# P09_Ethernet.net
KiCad netlist of a schematic drawn in Altium Designer
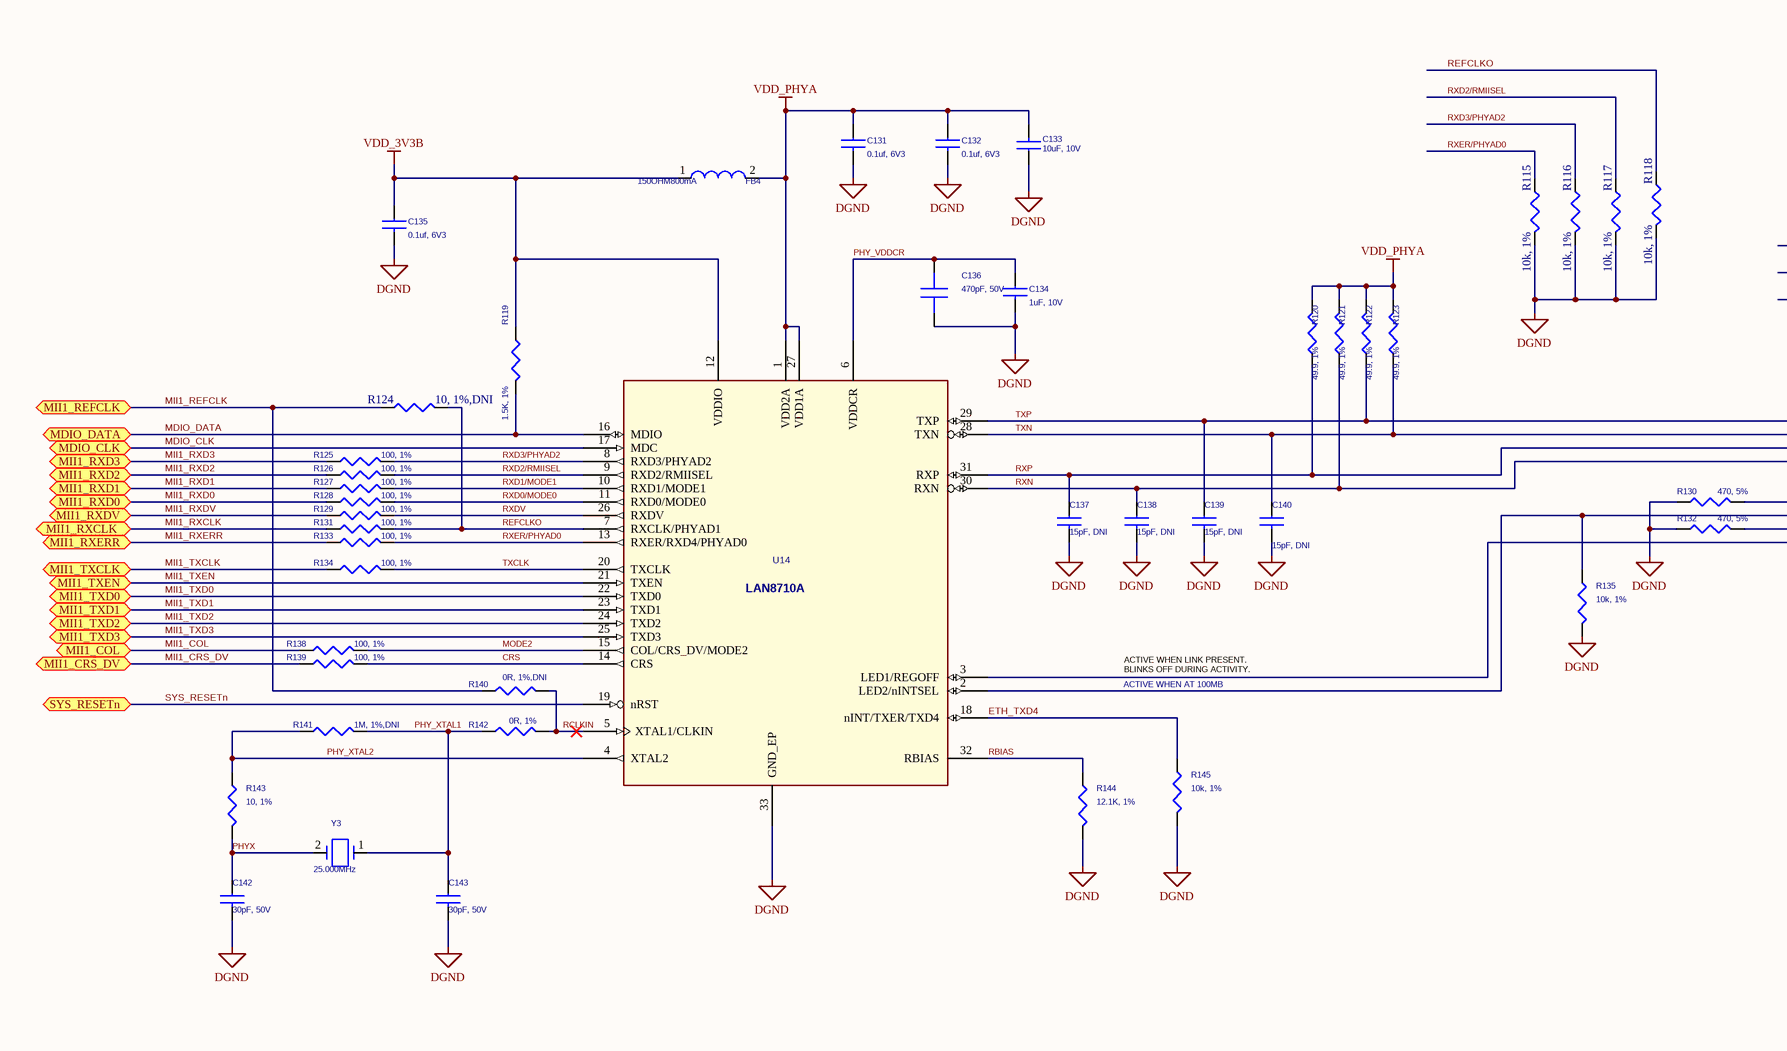
[diagram p0: P09_Ethernet.SchDoc, left]
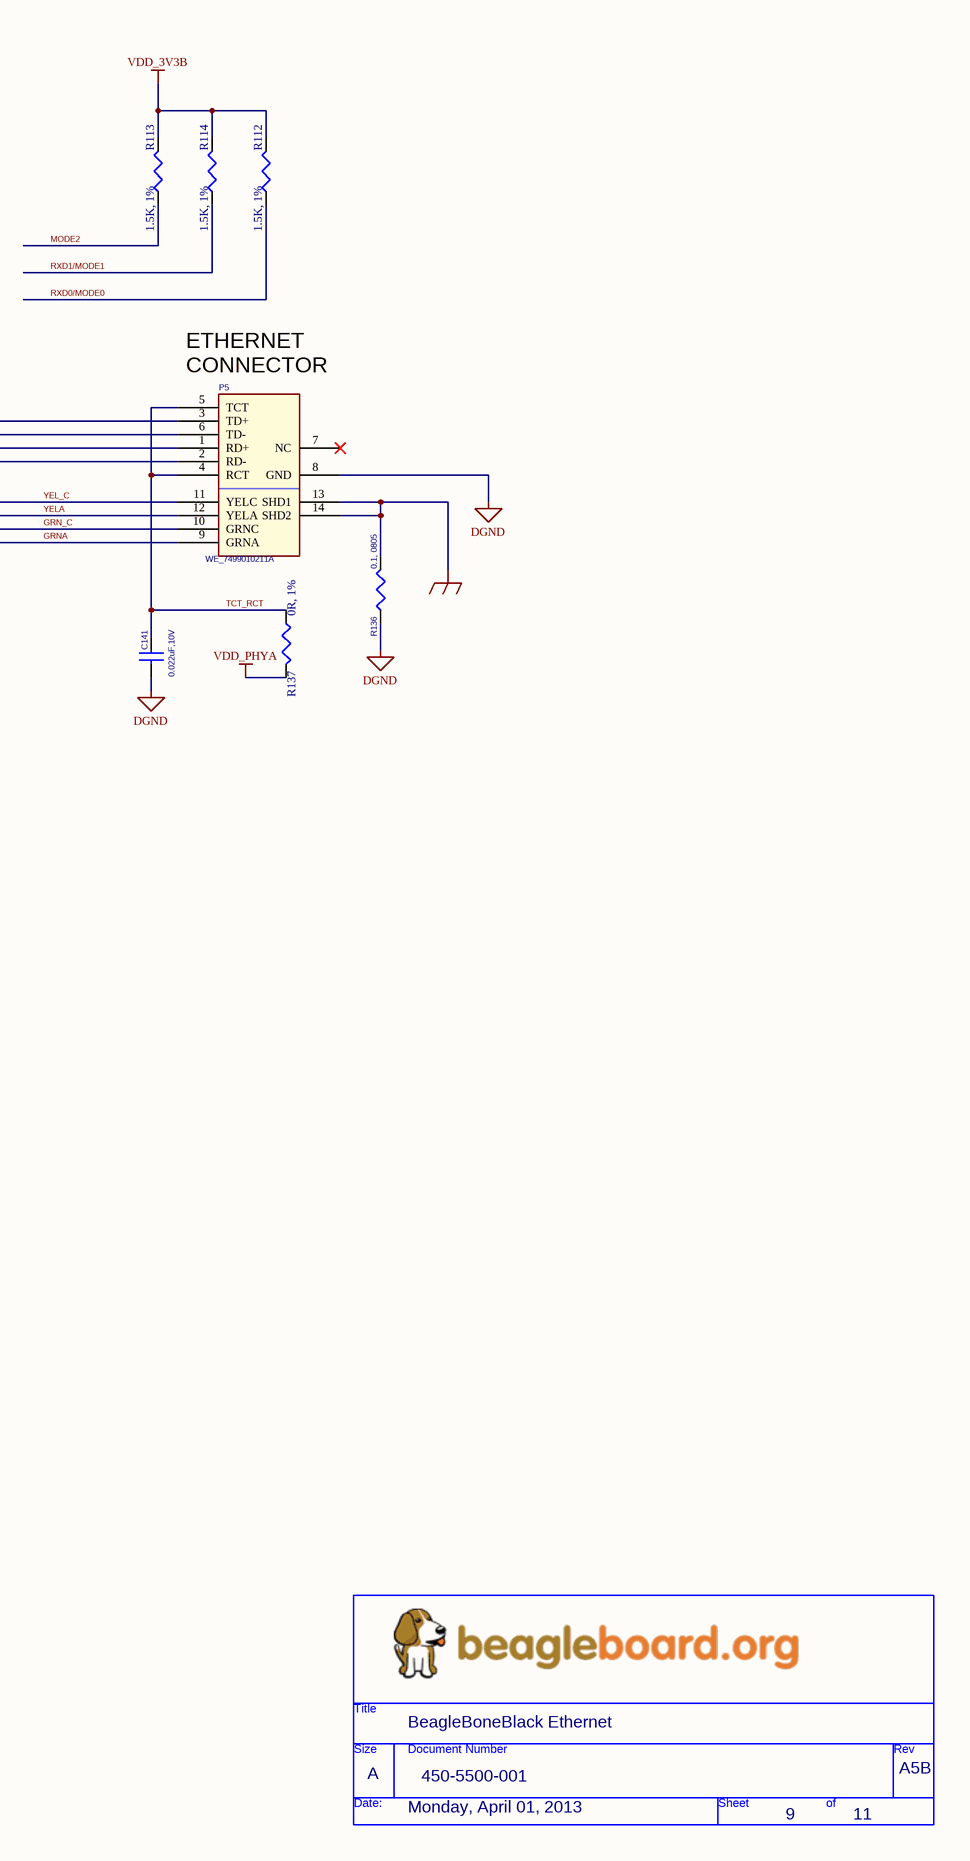
[diagram p1: P09_Ethernet.SchDoc, right]

(export (version "E")
  (design (tool "Eeschema 10.0.6"))
  (components
    (comp (ref "C131")
      (value "0.1uf, 6V3")
      (footprint "402")
      (description "CAP CER 0.1UF 6.3V 10% X5R 0402")
      (fields
        (field (name "MANUFACTURER") "TDK Corporation")
        (field (name "MANUFACTURER PART NUMBER") "C1005X5R0J104K050BA")
      )
      (libsource (lib "BEAGLEBONEBLACK_REV A5B") (part "CAP_0.1uF_X7R_16V_10% 0402"))
    )
    (comp (ref "C132")
      (value "0.1uf, 6V3")
      (footprint "402")
      (description "CAP CER 0.1UF 6.3V 10% X5R 0402")
      (fields
        (field (name "MANUFACTURER") "TDK Corporation")
        (field (name "MANUFACTURER PART NUMBER") "C1005X5R0J104K050BA")
      )
      (libsource (lib "BEAGLEBONEBLACK_REV A5B") (part "CAP_0.1uF_X7R_16V_10% 0402"))
    )
    (comp (ref "C133")
      (value "10uF, 10V")
      (footprint "805")
      (description "CAP CER 10UF 10V Y5V 0805")
      (fields
        (field (name "MANUFACTURER") "TDK Corporation")
        (field (name "MANUFACTURER PART NUMBER") "C2012Y5V1A106Z")
      )
      (libsource (lib "BEAGLEBONEBLACK_REV A5B") (part "CAP_4.7uF_X5R_6.3V_10%_0603"))
    )
    (comp (ref "C134")
      (value "1uF, 10V")
      (footprint "402")
      (description "CAP CER 1UF 10V 10% X5R 0402")
      (fields
        (field (name "MANUFACTURER") "AVX Corporation")
        (field (name "MANUFACTURER PART NUMBER") "0402ZD105KAT2A")
      )
      (libsource (lib "BEAGLEBONEBLACK_REV A5B") (part "CAP_1.0UF_X5R_10V_10%_0402"))
    )
    (comp (ref "C135")
      (value "0.1uf, 6V3")
      (footprint "402")
      (description "CAP CER 0.1UF 6.3V 10% X5R 0402")
      (fields
        (field (name "MANUFACTURER") "TDK Corporation")
        (field (name "MANUFACTURER PART NUMBER") "C1005X5R0J104K050BA")
      )
      (libsource (lib "BEAGLEBONEBLACK_REV A5B") (part "CAP_0.1uF_X7R_16V_10% 0402"))
    )
    (comp (ref "C136")
      (value "470pF, 50V")
      (footprint "402")
      (description "CAP CER 470PF 50V 10% X7R 0402")
      (fields
        (field (name "MANUFACTURER") "Murata Electronics North America")
        (field (name "MANUFACTURER PART NUMBER") "GRM155R71H471KA01D")
      )
      (libsource (lib "BEAGLEBONEBLACK_REV A5B") (part "470pF/5%/50V/C0G/0603_0"))
    )
    (comp (ref "C137")
      (value "15pF, DNI")
      (footprint "402")
      (description "CAP CER 15PF 50V 5% NP0 0402")
      (fields
        (field (name "MANUFACTURER") "TDK Corporation")
        (field (name "MANUFACTURER PART NUMBER") "C1005C0G1H150J050BA")
      )
      (libsource (lib "BEAGLEBONEBLACK_REV A5B") (part "CAP_0402_100pF_COG_50V"))
    )
    (comp (ref "C138")
      (value "15pF, DNI")
      (footprint "402")
      (description "CAP CER 15PF 50V 5% NP0 0402")
      (fields
        (field (name "MANUFACTURER") "TDK Corporation")
        (field (name "MANUFACTURER PART NUMBER") "C1005C0G1H150J050BA")
      )
      (libsource (lib "BEAGLEBONEBLACK_REV A5B") (part "CAP_0402_100pF_COG_50V"))
    )
    (comp (ref "C139")
      (value "15pF, DNI")
      (footprint "402")
      (description "CAP CER 15PF 50V 5% NP0 0402")
      (fields
        (field (name "MANUFACTURER") "TDK Corporation")
        (field (name "MANUFACTURER PART NUMBER") "C1005C0G1H150J050BA")
      )
      (libsource (lib "BEAGLEBONEBLACK_REV A5B") (part "CAP_0402_100pF_COG_50V"))
    )
    (comp (ref "C140")
      (value "15pF, DNI")
      (footprint "402")
      (description "CAP CER 15PF 50V 5% NP0 0402")
      (fields
        (field (name "MANUFACTURER") "TDK Corporation")
        (field (name "MANUFACTURER PART NUMBER") "C1005C0G1H150J050BA")
      )
      (libsource (lib "BEAGLEBONEBLACK_REV A5B") (part "CAP_0402_100pF_COG_50V"))
    )
    (comp (ref "C141")
      (value "0.022uF,10V")
      (footprint "402")
      (description "CAP CER 0.022UF 10V 10% X7R 0402")
      (fields
        (field (name "MANUFACTURER") "Taiyo Yuden")
        (field (name "MANUFACTURER PART NUMBER") "LMK105B7223KV-F")
      )
      (libsource (lib "BEAGLEBONEBLACK_REV A5B") (part "CAP_0402_0.1uf_X5R_10V"))
    )
    (comp (ref "C142")
      (value "30pF, 50V")
      (footprint "402")
      (description "CAP CER 30PF 50V 5% NP0 0402")
      (fields
        (field (name "MANUFACTURER") "TDK Corporation")
        (field (name "MANUFACTURER PART NUMBER") "C1005C0G1H300J")
      )
      (libsource (lib "BEAGLEBONEBLACK_REV A5B") (part "CAP_30PF_COG_50V_5%_0402"))
    )
    (comp (ref "C143")
      (value "30pF, 50V")
      (footprint "402")
      (description "CAP CER 30PF 50V 5% NP0 0402")
      (fields
        (field (name "MANUFACTURER") "TDK Corporation")
        (field (name "MANUFACTURER PART NUMBER") "C1005C0G1H300J")
      )
      (libsource (lib "BEAGLEBONEBLACK_REV A5B") (part "CAP_30PF_COG_50V_5%_0402"))
    )
    (comp (ref "FB4")
      (value "150OHM800mA")
      (footprint "SM-7351-IND-0805")
      (description "FERRITE 800MA 150 OHM 0805 SMD")
      (fields (field (name "MFR") "Steward") (field (name "TIINTPARTNUMBER") "1L0010"))
      (libsource (lib "BEAGLEBONEBLACK_REV A5B") (part "FER_180_200_0"))
    )
    (comp (ref "P5")
      (value "WE_7499010211A")
      (description "WE-RJ45 LAN Transformer")
      (libsource (lib "BEAGLEBONEBLACK_REV A5B") (part "CONN_RJ45_MAG_WE_0"))
    )
    (comp (ref "R112")
      (value "1.5K, 1%")
      (footprint "402")
      (description "RES 1.50K OHM 1/16W 1% 0402 SMD")
      (fields
        (field (name "MANUFACTURER") "Yageo")
        (field (name "MANUFACTURER PART NUMBER") "RC0402FR-071K5L")
      )
      (libsource (lib "BEAGLEBONEBLACK_REV A5B") (part "RES_10K_1/16W_1%_0402"))
    )
    (comp (ref "R113")
      (value "1.5K, 1%")
      (footprint "402")
      (description "RES 1.50K OHM 1/16W 1% 0402 SMD")
      (fields
        (field (name "MANUFACTURER") "Yageo")
        (field (name "MANUFACTURER PART NUMBER") "RC0402FR-071K5L")
      )
      (libsource (lib "BEAGLEBONEBLACK_REV A5B") (part "RES_10K_1/16W_1%_0402"))
    )
    (comp (ref "R114")
      (value "1.5K, 1%")
      (footprint "402")
      (description "RES 1.50K OHM 1/16W 1% 0402 SMD")
      (fields
        (field (name "MANUFACTURER") "Yageo")
        (field (name "MANUFACTURER PART NUMBER") "RC0402FR-071K5L")
      )
      (libsource (lib "BEAGLEBONEBLACK_REV A5B") (part "RES_10K_1/16W_1%_0402"))
    )
    (comp (ref "R115")
      (value "10k, 1%")
      (footprint "402")
      (description "RES 10K OHM 1/16W 5% 0402 SMD")
      (fields
        (field (name "MANUFACTURER") "Rohm Semiconductor")
        (field (name "MANUFACTURER PART NUMBER") "MCR01MZPJ103")
      )
      (libsource (lib "BEAGLEBONEBLACK_REV A5B") (part "RES_10K_1/16W_1%_0402"))
    )
    (comp (ref "R116")
      (value "10k, 1%")
      (footprint "402")
      (description "RES 10K OHM 1/16W 5% 0402 SMD")
      (fields
        (field (name "MANUFACTURER") "Rohm Semiconductor")
        (field (name "MANUFACTURER PART NUMBER") "MCR01MZPJ103")
      )
      (libsource (lib "BEAGLEBONEBLACK_REV A5B") (part "RES_10K_1/16W_1%_0402"))
    )
    (comp (ref "R117")
      (value "10k, 1%")
      (footprint "402")
      (description "RES 10K OHM 1/16W 5% 0402 SMD")
      (fields
        (field (name "MANUFACTURER") "Rohm Semiconductor")
        (field (name "MANUFACTURER PART NUMBER") "MCR01MZPJ103")
      )
      (libsource (lib "BEAGLEBONEBLACK_REV A5B") (part "RES_10K_1/16W_1%_0402"))
    )
    (comp (ref "R118")
      (value "10k, 1%")
      (footprint "402")
      (description "RES 10K OHM 1/16W 5% 0402 SMD")
      (fields
        (field (name "MANUFACTURER") "Rohm Semiconductor")
        (field (name "MANUFACTURER PART NUMBER") "MCR01MZPJ103")
      )
      (libsource (lib "BEAGLEBONEBLACK_REV A5B") (part "RES_10K_1/16W_1%_0402"))
    )
    (comp (ref "R119")
      (value "1.5K, 1%")
      (footprint "402")
      (description "RES 1.50K OHM 1/16W 1% 0402 SMD")
      (fields
        (field (name "MANUFACTURER") "Yageo")
        (field (name "MANUFACTURER PART NUMBER") "RC0402FR-071K5L")
      )
      (libsource (lib "BEAGLEBONEBLACK_REV A5B") (part "RES_1.5K_1/16W_5%_0402"))
    )
    (comp (ref "R120")
      (value "49.9, 1%")
      (footprint "402")
      (description "RES 49.9 OHM 1/16W 1% 0402 SMD")
      (fields
        (field (name "MANUFACTURER") "Yageo")
        (field (name "MANUFACTURER PART NUMBER") "RC0402FR-0749R9L")
      )
      (libsource (lib "BEAGLEBONEBLACK_REV A5B") (part "RES_4.7K_0402"))
    )
    (comp (ref "R121")
      (value "49.9, 1%")
      (footprint "402")
      (description "RES 49.9 OHM 1/16W 1% 0402 SMD")
      (fields
        (field (name "MANUFACTURER") "Yageo")
        (field (name "MANUFACTURER PART NUMBER") "RC0402FR-0749R9L")
      )
      (libsource (lib "BEAGLEBONEBLACK_REV A5B") (part "RES_4.7K_0402"))
    )
    (comp (ref "R122")
      (value "49.9, 1%")
      (footprint "402")
      (description "RES 49.9 OHM 1/16W 1% 0402 SMD")
      (fields
        (field (name "MANUFACTURER") "Yageo")
        (field (name "MANUFACTURER PART NUMBER") "RC0402FR-0749R9L")
      )
      (libsource (lib "BEAGLEBONEBLACK_REV A5B") (part "RES_4.7K_0402"))
    )
    (comp (ref "R123")
      (value "49.9, 1%")
      (footprint "402")
      (description "RES 49.9 OHM 1/16W 1% 0402 SMD")
      (fields
        (field (name "MANUFACTURER") "Yageo")
        (field (name "MANUFACTURER PART NUMBER") "RC0402FR-0749R9L")
      )
      (libsource (lib "BEAGLEBONEBLACK_REV A5B") (part "RES_4.7K_0402"))
    )
    (comp (ref "R124")
      (value "10, 1%,DNI")
      (footprint "402")
      (description "Resistor 10Kohm 1/16W 1% 0402")
      (fields
        (field (name "MANUFACTURER") "Stackpole Electronics Inc")
        (field (name "MANUFACTURER PART NUMBER") "RMCF0402FT10R0")
      )
      (libsource (lib "BEAGLEBONEBLACK_REV A5B") (part "RES_10K_1/16W_1%_0402"))
    )
    (comp (ref "R125")
      (value "100, 1%")
      (footprint "402")
      (description "RES 100 OHM 1/10W 5% 0402 SMD")
      (fields
        (field (name "PART#") "Rohm MCR03EZPFX1000")
        (field (name "MANUFACTURER") "Panasonic Electronic Components")
      )
      (libsource (lib "BEAGLEBONEBLACK_REV A5B") (part "100-1/10W-1%-0603_4"))
    )
    (comp (ref "R126")
      (value "100, 1%")
      (footprint "402")
      (description "RES 100 OHM 1/10W 5% 0402 SMD")
      (fields
        (field (name "PART#") "Rohm MCR03EZPFX1000")
        (field (name "MANUFACTURER") "Panasonic Electronic Components")
      )
      (libsource (lib "BEAGLEBONEBLACK_REV A5B") (part "100-1/10W-1%-0603_4"))
    )
    (comp (ref "R127")
      (value "100, 1%")
      (footprint "402")
      (description "RES 100 OHM 1/10W 5% 0402 SMD")
      (fields
        (field (name "MANUFACTURER") "Panasonic Electronic Components")
        (field (name "MANUFACTURER PART NUMBER") "ERJ-2RKF1000X")
      )
      (libsource (lib "BEAGLEBONEBLACK_REV A5B") (part "RES_100_1/10W_5%_0402"))
    )
    (comp (ref "R128")
      (value "100, 1%")
      (footprint "402")
      (description "RES 100 OHM 1/10W 5% 0402 SMD")
      (fields
        (field (name "MANUFACTURER") "Panasonic Electronic Components")
        (field (name "MANUFACTURER PART NUMBER") "ERJ-2RKF1000X")
      )
      (libsource (lib "BEAGLEBONEBLACK_REV A5B") (part "RES_100_1/10W_5%_0402"))
    )
    (comp (ref "R129")
      (value "100, 1%")
      (footprint "402")
      (description "RES 100 OHM 1/10W 5% 0402 SMD")
      (fields
        (field (name "PART#") "Rohm MCR03EZPFX1000")
        (field (name "MANUFACTURER") "Panasonic Electronic Components")
      )
      (libsource (lib "BEAGLEBONEBLACK_REV A5B") (part "100-1/10W-1%-0603_4"))
    )
    (comp (ref "R130")
      (value "470, 5%")
      (footprint "402")
      (description "RES 470 OHM 1/10W 5% 0402 SMD")
      (fields
        (field (name "MANUFACTURER") "Panasonic Electronic Components")
        (field (name "MANUFACTURER PART NUMBER") "ERJ-2GEJ471X")
      )
      (libsource (lib "BEAGLEBONEBLACK_REV A5B") (part "RES_470_1/10W_5%_0402"))
    )
    (comp (ref "R131")
      (value "100, 1%")
      (footprint "402")
      (description "RES 100 OHM 1/10W 5% 0402 SMD")
      (fields
        (field (name "MANUFACTURER") "Panasonic Electronic Components")
        (field (name "MANUFACTURER PART NUMBER") "ERJ-2RKF1000X")
      )
      (libsource (lib "BEAGLEBONEBLACK_REV A5B") (part "RES_100_1/10W_5%_0402"))
    )
    (comp (ref "R132")
      (value "470, 5%")
      (footprint "402")
      (description "RES 470 OHM 1/10W 5% 0402 SMD")
      (fields
        (field (name "MANUFACTURER") "Panasonic Electronic Components")
        (field (name "MANUFACTURER PART NUMBER") "ERJ-2GEJ471X")
      )
      (libsource (lib "BEAGLEBONEBLACK_REV A5B") (part "RES_470_1/10W_5%_0402"))
    )
    (comp (ref "R133")
      (value "100, 1%")
      (footprint "402")
      (description "RES 100 OHM 1/10W 5% 0402 SMD")
      (fields
        (field (name "MANUFACTURER") "Panasonic Electronic Components")
        (field (name "MANUFACTURER PART NUMBER") "ERJ-2RKF1000X")
      )
      (libsource (lib "BEAGLEBONEBLACK_REV A5B") (part "RES_100_1/10W_5%_0402"))
    )
    (comp (ref "R134")
      (value "100, 1%")
      (footprint "402")
      (description "RES 100 OHM 1/10W 5% 0402 SMD")
      (fields (field (name "PART#") "Rohm MCR03EZPFX1000") (field (name "TOLERANCE") "1%"))
      (libsource (lib "BEAGLEBONEBLACK_REV A5B") (part "100-1/10W-1%-0603_4"))
    )
    (comp (ref "R135")
      (value "10k, 1%")
      (footprint "402")
      (description "RES 10K OHM 1/16W 5% 0402 SMD")
      (fields
        (field (name "MANUFACTURER") "Rohm Semiconductor")
        (field (name "MANUFACTURER PART NUMBER") "MCR01MZPJ103")
      )
      (libsource (lib "BEAGLEBONEBLACK_REV A5B") (part "RES_10K_1/16W_1%_0402"))
    )
    (comp (ref "R136")
      (value "0.1, 0805")
      (description "RES .10 OHM 1/8W 5% 0805")
      (fields
        (field (name "MANUFACTURER") "CTS Resistor Products")
        (field (name "MANUFACTURER PART NUMBER") "73L3R10J")
      )
      (libsource (lib "BEAGLEBONEBLACK_REV A5B") (part "RES_0.1_0805"))
    )
    (comp (ref "R137")
      (value "0R, 1%")
      (footprint "402")
      (description "RES 0.0 OHM 1/16W 0402 SMD")
      (fields
        (field (name "MANUFACTURER") "Yageo")
        (field (name "MANUFACTURER PART NUMBER") "RC0402JR-070RL")
      )
      (libsource (lib "BEAGLEBONEBLACK_REV A5B") (part "RES_0_1/16W_1%_0402"))
    )
    (comp (ref "R138")
      (value "100, 1%")
      (footprint "402")
      (description "RES 100 OHM 1/10W 5% 0402 SMD")
      (fields (field (name "PART#") "Rohm MCR03EZPFX1000") (field (name "TOLERANCE") "1%"))
      (libsource (lib "BEAGLEBONEBLACK_REV A5B") (part "100-1/10W-1%-0603_4"))
    )
    (comp (ref "R139")
      (value "100, 1%")
      (footprint "402")
      (description "RES 100 OHM 1/10W 5% 0402 SMD")
      (fields
        (field (name "MANUFACTURER") "Panasonic Electronic Components")
        (field (name "MANUFACTURER PART NUMBER") "ERJ-2RKF1000X")
      )
      (libsource (lib "BEAGLEBONEBLACK_REV A5B") (part "RES_100_1/10W_5%_0402"))
    )
    (comp (ref "R140")
      (value "0R, 1%,DNI")
      (footprint "402")
      (description "RES 0.0 OHM 1/16W 0402 SMD")
      (fields
        (field (name "MANUFACTURER") "Yageo")
        (field (name "MANUFACTURER PART NUMBER") "RC0402JR-070RL")
      )
      (libsource (lib "BEAGLEBONEBLACK_REV A5B") (part "RES_0_1/16W_1%_0402"))
    )
    (comp (ref "R141")
      (value "1M, 1%,DNI")
      (footprint "402")
      (description "RES 1M OHM 1/16W 1% 0402 SMD")
      (fields
        (field (name "MANUFACTURER") "Stackpole Electronics Inc")
        (field (name "MANUFACTURER PART NUMBER") "RMCF0402FT1M00")
      )
      (libsource (lib "BEAGLEBONEBLACK_REV A5B") (part "RES_1M_1/16W_1%_0402"))
    )
    (comp (ref "R142")
      (value "0R, 1%")
      (footprint "402")
      (description "RES 0.0 OHM 1/16W 0402 SMD")
      (fields
        (field (name "MANUFACTURER") "Yageo")
        (field (name "MANUFACTURER PART NUMBER") "RC0402JR-070RL")
      )
      (libsource (lib "BEAGLEBONEBLACK_REV A5B") (part "RES_0_1/16W_1%_0402"))
    )
    (comp (ref "R143")
      (value "10, 1%")
      (footprint "402")
      (description "RES 10 OHM 1/16W 1% 0402 SMD")
      (fields
        (field (name "MANUFACTURER") "Stackpole Electronics Inc")
        (field (name "MANUFACTURER PART NUMBER") "RMCF0402FT10R0")
      )
      (libsource (lib "BEAGLEBONEBLACK_REV A5B") (part "RES_10K_1/16W_1%_0402"))
    )
    (comp (ref "R144")
      (value "12.1K, 1%")
      (footprint "402")
      (description "RES 12.1K OHM 1/16W 1% 0402 SMD")
      (fields
        (field (name "MANUFACTURER") "Yageo")
        (field (name "MANUFACTURER PART NUMBER") "RC0402FR-0712K1L")
      )
      (libsource (lib "BEAGLEBONEBLACK_REV A5B") (part "RES_12.1K_1/16W_1%_0402"))
    )
    (comp (ref "R145")
      (value "10k, 1%")
      (footprint "402")
      (description "RES 10K OHM 1/16W 5% 0402 SMD")
      (fields
        (field (name "MANUFACTURER") "Rohm Semiconductor")
        (field (name "MANUFACTURER PART NUMBER") "MCR01MZPJ103")
      )
      (libsource (lib "BEAGLEBONEBLACK_REV A5B") (part "RES_10K_1/16W_1%_0402"))
    )
    (comp (ref "U14")
      (value "LAN8710A")
      (footprint "QFN32_5X5MM_EP3P3MM")
      (description "Ethernet ICs 10/100 Ethernet XCVR w/HPAutoMDIX FlexPwr")
      (fields (field (name "PART#") "SMSC LAN8710A-EZK") (field (name "MANUFACTURER") "Microchip Technology"))
      (libsource (lib "BEAGLEBONEBLACK_REV A5B") (part "LAN8710 QFN32_1"))
    )
    (comp (ref "Y3")
      (value "25.000MHz")
      (footprint "XTAL150SMD_125X196")
      (fields
        (field (name "MANUFACTURER") "Abracon Corporation")
        (field (name "MANUFACTURER PART NUMBER") "ABM3-25.000MHZ-B2-T")
      )
      (libsource (lib "BEAGLEBONEBLACK_REV A5B") (part "Suntsu ITEMP 25MHz _0.005% 20pf"))
    )
  )
  (nets
    (net (code "1") (name "/CRS") (class "Default")
      (node (ref "R139") (pin "2") (pinfunction "2_2") (pintype "passive"))
      (node (ref "U14") (pin "14") (pinfunction "CRS_14") (pintype "output"))
    )
    (net (code "2") (name "/ETH_TXD4") (class "Default")
      (node (ref "R145") (pin "1") (pinfunction "1_1") (pintype "passive"))
      (node (ref "U14") (pin "18") (pinfunction "nINT/TXER/TXD4_18") (pintype "bidirectional"))
    )
    (net (code "3") (name "/GRNA") (class "Default")
      (node (ref "P5") (pin "9") (pinfunction "GRNA_9") (pintype "passive"))
      (node (ref "U14") (pin "3") (pinfunction "LED1/REGOFF_3") (pintype "bidirectional"))
    )
    (net (code "4") (name "/GRN_C") (class "Default")
      (node (ref "P5") (pin "10") (pinfunction "GRNC_10") (pintype "passive"))
      (node (ref "R132") (pin "2") (pinfunction "2_2") (pintype "passive"))
    )
    (net (code "5") (name "/MDIO_CLK") (class "Default")
      (node (ref "U14") (pin "17") (pinfunction "MDC_17") (pintype "input"))
    )
    (net (code "6") (name "/MDIO_DATA") (class "Default")
      (node (ref "R119") (pin "2") (pinfunction "2_2") (pintype "passive"))
      (node (ref "U14") (pin "16") (pinfunction "MDIO_16") (pintype "bidirectional"))
    )
    (net (code "7") (name "/MII1_COL") (class "Default")
      (node (ref "R138") (pin "1") (pinfunction "1_1") (pintype "passive"))
    )
    (net (code "8") (name "/MII1_CRS_DV") (class "Default")
      (node (ref "R139") (pin "1") (pinfunction "1_1") (pintype "passive"))
    )
    (net (code "9") (name "/MII1_REFCLK") (class "Default")
      (node (ref "R124") (pin "1") (pinfunction "1_1") (pintype "passive"))
      (node (ref "R140") (pin "1") (pinfunction "1_1") (pintype "passive"))
    )
    (net (code "10") (name "/MII1_RXCLK") (class "Default")
      (node (ref "R131") (pin "1") (pinfunction "1_1") (pintype "passive"))
    )
    (net (code "11") (name "/MII1_RXD0") (class "Default")
      (node (ref "R128") (pin "1") (pinfunction "1_1") (pintype "passive"))
    )
    (net (code "12") (name "/MII1_RXD1") (class "Default")
      (node (ref "R127") (pin "1") (pinfunction "1_1") (pintype "passive"))
    )
    (net (code "13") (name "/MII1_RXD2") (class "Default")
      (node (ref "R126") (pin "1") (pinfunction "1_1") (pintype "passive"))
    )
    (net (code "14") (name "/MII1_RXD3") (class "Default")
      (node (ref "R125") (pin "1") (pinfunction "1_1") (pintype "passive"))
    )
    (net (code "15") (name "/MII1_RXDV") (class "Default")
      (node (ref "R129") (pin "1") (pinfunction "1_1") (pintype "passive"))
    )
    (net (code "16") (name "/MII1_RXERR") (class "Default")
      (node (ref "R133") (pin "1") (pinfunction "1_1") (pintype "passive"))
    )
    (net (code "17") (name "/MII1_TXCLK") (class "Default")
      (node (ref "R134") (pin "1") (pinfunction "1_1") (pintype "passive"))
    )
    (net (code "18") (name "/MII1_TXD0") (class "Default")
      (node (ref "U14") (pin "22") (pinfunction "TXD0_22") (pintype "input"))
    )
    (net (code "19") (name "/MII1_TXD1") (class "Default")
      (node (ref "U14") (pin "23") (pinfunction "TXD1_23") (pintype "input"))
    )
    (net (code "20") (name "/MII1_TXD2") (class "Default")
      (node (ref "U14") (pin "24") (pinfunction "TXD2_24") (pintype "input"))
    )
    (net (code "21") (name "/MII1_TXD3") (class "Default")
      (node (ref "U14") (pin "25") (pinfunction "TXD3_25") (pintype "input"))
    )
    (net (code "22") (name "/MII1_TXEN") (class "Default")
      (node (ref "U14") (pin "21") (pinfunction "TXEN_21") (pintype "input"))
    )
    (net (code "23") (name "/MODE2") (class "Default")
      (node (ref "R113") (pin "1") (pinfunction "1_1") (pintype "passive"))
      (node (ref "R138") (pin "2") (pinfunction "2_2") (pintype "passive"))
      (node (ref "U14") (pin "15") (pinfunction "COL/CRS_DV/MODE2_15") (pintype "output"))
    )
    (net (code "24") (name "/PHYX") (class "Default")
      (node (ref "C142") (pin "1") (pinfunction "1_1") (pintype "passive"))
      (node (ref "R143") (pin "2") (pinfunction "2_2") (pintype "passive"))
      (node (ref "Y3") (pin "2") (pinfunction "2_2") (pintype "passive"))
    )
    (net (code "25") (name "/PHY_VDDCR") (class "Default")
      (node (ref "C134") (pin "1") (pinfunction "1_1") (pintype "passive"))
      (node (ref "C136") (pin "1") (pinfunction "1_1") (pintype "passive"))
      (node (ref "U14") (pin "6") (pinfunction "VDDCR_6") (pintype "power_in"))
    )
    (net (code "26") (name "/PHY_XTAL1") (class "Default")
      (node (ref "C143") (pin "1") (pinfunction "1_1") (pintype "passive"))
      (node (ref "R141") (pin "2") (pinfunction "2_2") (pintype "passive"))
      (node (ref "R142") (pin "1") (pinfunction "1_1") (pintype "passive"))
      (node (ref "Y3") (pin "1") (pinfunction "1_1") (pintype "passive"))
    )
    (net (code "27") (name "/PHY_XTAL2") (class "Default")
      (node (ref "R141") (pin "1") (pinfunction "1_1") (pintype "passive"))
      (node (ref "R143") (pin "1") (pinfunction "1_1") (pintype "passive"))
      (node (ref "U14") (pin "4") (pinfunction "XTAL2_4") (pintype "output"))
    )
    (net (code "28") (name "/RBIAS") (class "Default")
      (node (ref "R144") (pin "1") (pinfunction "1_1") (pintype "passive"))
      (node (ref "U14") (pin "32") (pinfunction "RBIAS_32") (pintype "passive"))
    )
    (net (code "29") (name "/RCLKIN") (class "Default")
      (node (ref "R140") (pin "2") (pinfunction "2_2") (pintype "passive"))
      (node (ref "R142") (pin "2") (pinfunction "2_2") (pintype "passive"))
      (node (ref "U14") (pin "5") (pinfunction "XTAL1/CLKIN_5") (pintype "input"))
    )
    (net (code "30") (name "/REFCLKO") (class "Default")
      (node (ref "R118") (pin "1") (pinfunction "1_1") (pintype "passive"))
      (node (ref "R124") (pin "2") (pinfunction "2_2") (pintype "passive"))
      (node (ref "R131") (pin "2") (pinfunction "2_2") (pintype "passive"))
      (node (ref "U14") (pin "7") (pinfunction "RXCLK/PHYAD1_7") (pintype "output"))
    )
    (net (code "31") (name "/RXD0{slash}MODE0") (class "Default")
      (node (ref "R112") (pin "1") (pinfunction "1_1") (pintype "passive"))
      (node (ref "R128") (pin "2") (pinfunction "2_2") (pintype "passive"))
      (node (ref "U14") (pin "11") (pinfunction "RXD0/MODE0_11") (pintype "output"))
    )
    (net (code "32") (name "/RXD1{slash}MODE1") (class "Default")
      (node (ref "R114") (pin "1") (pinfunction "1_1") (pintype "passive"))
      (node (ref "R127") (pin "2") (pinfunction "2_2") (pintype "passive"))
      (node (ref "U14") (pin "10") (pinfunction "RXD1/MODE1_10") (pintype "output"))
    )
    (net (code "33") (name "/RXD2{slash}RMIISEL") (class "Default")
      (node (ref "R117") (pin "1") (pinfunction "1_1") (pintype "passive"))
      (node (ref "R126") (pin "2") (pinfunction "2_2") (pintype "passive"))
      (node (ref "U14") (pin "9") (pinfunction "RXD2/RMIISEL_9") (pintype "output"))
    )
    (net (code "34") (name "/RXD3{slash}PHYAD2") (class "Default")
      (node (ref "R116") (pin "1") (pinfunction "1_1") (pintype "passive"))
      (node (ref "R125") (pin "2") (pinfunction "2_2") (pintype "passive"))
      (node (ref "U14") (pin "8") (pinfunction "RXD3/PHYAD2_8") (pintype "output"))
    )
    (net (code "35") (name "/RXDV") (class "Default")
      (node (ref "R129") (pin "2") (pinfunction "2_2") (pintype "passive"))
      (node (ref "U14") (pin "26") (pinfunction "RXDV_26") (pintype "output"))
    )
    (net (code "36") (name "/RXER{slash}PHYAD0") (class "Default")
      (node (ref "R115") (pin "1") (pinfunction "1_1") (pintype "passive"))
      (node (ref "R133") (pin "2") (pinfunction "2_2") (pintype "passive"))
      (node (ref "U14") (pin "13") (pinfunction "RXER/RXD4/PHYAD0_13") (pintype "output"))
    )
    (net (code "37") (name "/RXN") (class "Default")
      (node (ref "C138") (pin "1") (pinfunction "1_1") (pintype "passive"))
      (node (ref "P5") (pin "2") (pinfunction "RD-_2") (pintype "passive"))
      (node (ref "R121") (pin "1") (pinfunction "1_1") (pintype "passive"))
      (node (ref "U14") (pin "30") (pinfunction "RXN_30") (pintype "bidirectional"))
    )
    (net (code "38") (name "/RXP") (class "Default")
      (node (ref "C137") (pin "1") (pinfunction "1_1") (pintype "passive"))
      (node (ref "P5") (pin "1") (pinfunction "RD+_1") (pintype "passive"))
      (node (ref "R120") (pin "1") (pinfunction "1_1") (pintype "passive"))
      (node (ref "U14") (pin "31") (pinfunction "RXP_31") (pintype "bidirectional"))
    )
    (net (code "39") (name "/SYS_RESETn") (class "Default")
      (node (ref "U14") (pin "19") (pinfunction "nRST_19") (pintype "input"))
    )
    (net (code "40") (name "/TCT_RCT") (class "Default")
      (node (ref "C141") (pin "1") (pinfunction "1_1") (pintype "passive"))
      (node (ref "P5") (pin "4") (pinfunction "RCT_4") (pintype "passive"))
      (node (ref "P5") (pin "5") (pinfunction "TCT_5") (pintype "passive"))
      (node (ref "R137") (pin "1") (pinfunction "1_1") (pintype "passive"))
    )
    (net (code "41") (name "/TXCLK") (class "Default")
      (node (ref "R134") (pin "2") (pinfunction "2_2") (pintype "passive"))
      (node (ref "U14") (pin "20") (pinfunction "TXCLK_20") (pintype "output"))
    )
    (net (code "42") (name "/TXN") (class "Default")
      (node (ref "C140") (pin "1") (pinfunction "1_1") (pintype "passive"))
      (node (ref "P5") (pin "6") (pinfunction "TD-_6") (pintype "passive"))
      (node (ref "R123") (pin "1") (pinfunction "1_1") (pintype "passive"))
      (node (ref "U14") (pin "28") (pinfunction "TXN_28") (pintype "bidirectional"))
    )
    (net (code "43") (name "/TXP") (class "Default")
      (node (ref "C139") (pin "1") (pinfunction "1_1") (pintype "passive"))
      (node (ref "P5") (pin "3") (pinfunction "TD+_3") (pintype "passive"))
      (node (ref "R122") (pin "1") (pinfunction "1_1") (pintype "passive"))
      (node (ref "U14") (pin "29") (pinfunction "TXP_29") (pintype "bidirectional"))
    )
    (net (code "44") (name "/YELA") (class "Default")
      (node (ref "P5") (pin "12") (pinfunction "YELA_12") (pintype "passive"))
      (node (ref "R135") (pin "1") (pinfunction "1_1") (pintype "passive"))
      (node (ref "U14") (pin "2") (pinfunction "LED2/nINTSEL_2") (pintype "bidirectional"))
    )
    (net (code "45") (name "/YEL_C") (class "Default")
      (node (ref "P5") (pin "11") (pinfunction "YELC_11") (pintype "passive"))
      (node (ref "R130") (pin "2") (pinfunction "2_2") (pintype "passive"))
    )
    (net (code "46") (name "DGND") (class "Default")
      (node (ref "C131") (pin "2") (pinfunction "2_2") (pintype "passive"))
      (node (ref "C132") (pin "2") (pinfunction "2_2") (pintype "passive"))
      (node (ref "C133") (pin "1") (pinfunction "1_1") (pintype "passive"))
      (node (ref "C134") (pin "2") (pinfunction "2_2") (pintype "passive"))
      (node (ref "C135") (pin "2") (pinfunction "2_2") (pintype "passive"))
      (node (ref "C136") (pin "2") (pinfunction "2_2") (pintype "passive"))
      (node (ref "C137") (pin "2") (pinfunction "2_2") (pintype "passive"))
      (node (ref "C138") (pin "2") (pinfunction "2_2") (pintype "passive"))
      (node (ref "C139") (pin "2") (pinfunction "2_2") (pintype "passive"))
      (node (ref "C140") (pin "2") (pinfunction "2_2") (pintype "passive"))
      (node (ref "C141") (pin "2") (pinfunction "2_2") (pintype "passive"))
      (node (ref "C142") (pin "2") (pinfunction "2_2") (pintype "passive"))
      (node (ref "C143") (pin "2") (pinfunction "2_2") (pintype "passive"))
      (node (ref "P5") (pin "8") (pinfunction "GND_8") (pintype "passive"))
      (node (ref "R115") (pin "2") (pinfunction "2_2") (pintype "passive"))
      (node (ref "R116") (pin "2") (pinfunction "2_2") (pintype "passive"))
      (node (ref "R117") (pin "2") (pinfunction "2_2") (pintype "passive"))
      (node (ref "R118") (pin "2") (pinfunction "2_2") (pintype "passive"))
      (node (ref "R130") (pin "1") (pinfunction "1_1") (pintype "passive"))
      (node (ref "R132") (pin "1") (pinfunction "1_1") (pintype "passive"))
      (node (ref "R135") (pin "2") (pinfunction "2_2") (pintype "passive"))
      (node (ref "R136") (pin "1") (pinfunction "1_1") (pintype "passive"))
      (node (ref "R144") (pin "2") (pinfunction "2_2") (pintype "passive"))
      (node (ref "R145") (pin "2") (pinfunction "2_2") (pintype "passive"))
      (node (ref "U14") (pin "33") (pinfunction "GND_EP_33") (pintype "power_in"))
    )
    (net (code "47") (name "GND_EARTH") (class "Default")
      (node (ref "P5") (pin "13") (pinfunction "SHD1_13") (pintype "passive"))
      (node (ref "P5") (pin "14") (pinfunction "SHD2_14") (pintype "passive"))
      (node (ref "R136") (pin "2") (pinfunction "2_2") (pintype "passive"))
    )
    (net (code "48") (name "VDD_3V3B") (class "Default")
      (node (ref "C135") (pin "1") (pinfunction "1_1") (pintype "passive"))
      (node (ref "FB4") (pin "1") (pinfunction "1_1") (pintype "passive"))
      (node (ref "R112") (pin "2") (pinfunction "2_2") (pintype "passive"))
      (node (ref "R113") (pin "2") (pinfunction "2_2") (pintype "passive"))
      (node (ref "R114") (pin "2") (pinfunction "2_2") (pintype "passive"))
      (node (ref "R119") (pin "1") (pinfunction "1_1") (pintype "passive"))
      (node (ref "U14") (pin "12") (pinfunction "VDDIO_12") (pintype "power_in"))
    )
    (net (code "49") (name "VDD_PHYA") (class "Default")
      (node (ref "C131") (pin "1") (pinfunction "1_1") (pintype "passive"))
      (node (ref "C132") (pin "1") (pinfunction "1_1") (pintype "passive"))
      (node (ref "C133") (pin "2") (pinfunction "2_2") (pintype "passive"))
      (node (ref "FB4") (pin "2") (pinfunction "2_2") (pintype "passive"))
      (node (ref "R120") (pin "2") (pinfunction "2_2") (pintype "passive"))
      (node (ref "R121") (pin "2") (pinfunction "2_2") (pintype "passive"))
      (node (ref "R122") (pin "2") (pinfunction "2_2") (pintype "passive"))
      (node (ref "R123") (pin "2") (pinfunction "2_2") (pintype "passive"))
      (node (ref "R137") (pin "2") (pinfunction "2_2") (pintype "passive"))
      (node (ref "U14") (pin "1") (pinfunction "VDD2A_1") (pintype "power_in"))
      (node (ref "U14") (pin "27") (pinfunction "VDD1A_27") (pintype "power_in"))
    )
    (net (code "50") (name "unconnected-(P5-NC-Pad7)") (class "Default")
      (node (ref "P5") (pin "7") (pinfunction "NC_7") (pintype "passive+no_connect"))
    )
  )
)
